# PulseTrainGenerator.net
KiCad netlist of a schematic drawn in Altium Designer
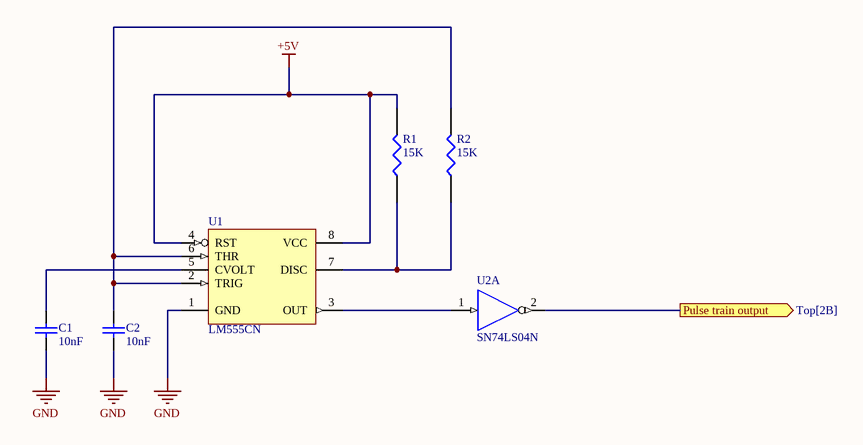
[diagram p0: PulseTrainGenerator.SchDoc]

(export (version "E")
  (design (tool "Eeschema 10.0.6"))
  (components
    (comp (ref "C1")
      (value "10nF")
      (description "Ceramic Capacitor")
      (fields (field (name "PUBLISHER") "Altium Limited"))
      (libsource (lib "ECET231SCHLIB_Rev01") (part "Cap"))
    )
    (comp (ref "C2")
      (value "10nF")
      (description "Ceramic Capacitor")
      (fields (field (name "PUBLISHER") "Altium Limited"))
      (libsource (lib "ECET231SCHLIB_Rev01") (part "Cap"))
    )
    (comp (ref "R1")
      (value "15K")
      (footprint "axial0.5")
      (description "Resistor")
      (libsource (lib "ECET231SCHLIB_Rev01") (part "RES1"))
    )
    (comp (ref "R2")
      (value "15K")
      (footprint "axial0.5")
      (description "Resistor")
      (libsource (lib "ECET231SCHLIB_Rev01") (part "RES1"))
    )
    (comp (ref "U1")
      (value "LM555CN")
      (footprint "DIP-8")
      (description "Timer")
      (fields (field (name "PUBLISHER") "Altium Limited"))
      (libsource (lib "ECET231SCHLIB_Rev01") (part "LM555CN"))
    )
    (comp (ref "U2")
      (value "SN74LS04N")
      (footprint "DIP14")
      (description "Hex Inverter")
      (fields (field (name "PUBLISHER") "Altium Limited"))
      (libsource (lib "ECET231SCHLIB_Rev01") (part "SN74LS04N"))
    )
  )
  (nets
    (net (code "1") (name "+5V") (class "Default")
      (node (ref "R1") (pin "2") (pinfunction "2_2") (pintype "passive"))
      (node (ref "U1") (pin "4") (pinfunction "RST_4") (pintype "input"))
      (node (ref "U1") (pin "8") (pinfunction "VCC_8") (pintype "power_in"))
    )
    (net (code "2") (name "/Pulse train output") (class "Default")
      (node (ref "U2") (pin "2") (pinfunction "Y_2") (pintype "output"))
    )
    (net (code "3") (name "GND") (class "Default")
      (node (ref "C1") (pin "1") (pinfunction "1_1") (pintype "passive"))
      (node (ref "C2") (pin "1") (pinfunction "1_1") (pintype "passive"))
      (node (ref "U1") (pin "1") (pinfunction "GND_1") (pintype "power_in"))
      (node (ref "U2") (pin "7") (pinfunction "GND_7") (pintype "power_in"))
    )
    (net (code "4") (name "Net-(U1-CVOLT)") (class "Default")
      (node (ref "C1") (pin "2") (pinfunction "2_2") (pintype "passive"))
      (node (ref "U1") (pin "5") (pinfunction "CVOLT_5") (pintype "passive"))
    )
    (net (code "5") (name "Net-(U1-DISC)") (class "Default")
      (node (ref "R1") (pin "1") (pinfunction "1_1") (pintype "passive"))
      (node (ref "R2") (pin "1") (pinfunction "1_1") (pintype "passive"))
      (node (ref "U1") (pin "7") (pinfunction "DISC_7") (pintype "open_collector"))
    )
    (net (code "6") (name "Net-(U1-OUT)") (class "Default")
      (node (ref "U1") (pin "3") (pinfunction "OUT_3") (pintype "output"))
      (node (ref "U2") (pin "1") (pinfunction "A_1") (pintype "input"))
    )
    (net (code "7") (name "Net-(U1-THR)") (class "Default")
      (node (ref "C2") (pin "2") (pinfunction "2_2") (pintype "passive"))
      (node (ref "R2") (pin "2") (pinfunction "2_2") (pintype "passive"))
      (node (ref "U1") (pin "2") (pinfunction "TRIG_2") (pintype "input"))
      (node (ref "U1") (pin "6") (pinfunction "THR_6") (pintype "input"))
    )
    (net (code "8") (name "VCC") (class "Default")
      (node (ref "U2") (pin "14") (pinfunction "VCC_14") (pintype "power_in"))
    )
  )
)
